# Connector.net
KiCad netlist of a schematic drawn in Altium Designer
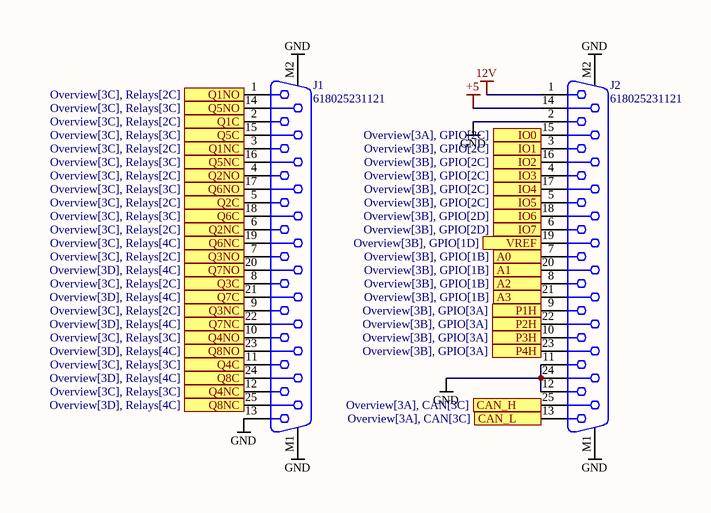
[diagram p0: Connector.SchDoc]

(export (version "E")
  (design (tool "Eeschema 10.0.6"))
  (components
    (comp (ref "J1")
      (value "618025231121")
      (footprint "618025231121")
      (libsource (lib "Altium Content Vault") (part "D-Sub_Female_25p"))
    )
    (comp (ref "J2")
      (value "618025231121")
      (footprint "618025231121")
      (libsource (lib "Altium Content Vault") (part "D-Sub_Female_25p"))
    )
  )
  (nets
    (net (code "1") (name "+5") (class "Default")
      (node (ref "J2") (pin "14") (pinfunction "14_14") (pintype "passive"))
    )
    (net (code "2") (name "/A0") (class "Default")
      (node (ref "J2") (pin "7") (pinfunction "7_7") (pintype "passive"))
    )
    (net (code "3") (name "/A1") (class "Default")
      (node (ref "J2") (pin "20") (pinfunction "20_20") (pintype "passive"))
    )
    (net (code "4") (name "/A2") (class "Default")
      (node (ref "J2") (pin "8") (pinfunction "8_8") (pintype "passive"))
    )
    (net (code "5") (name "/A3") (class "Default")
      (node (ref "J2") (pin "21") (pinfunction "21_21") (pintype "passive"))
    )
    (net (code "6") (name "/CAN_H") (class "Default")
      (node (ref "J2") (pin "25") (pinfunction "25_25") (pintype "passive"))
    )
    (net (code "7") (name "/CAN_L") (class "Default")
      (node (ref "J2") (pin "13") (pinfunction "13_13") (pintype "passive"))
    )
    (net (code "8") (name "/IO0") (class "Default")
      (node (ref "J2") (pin "15") (pinfunction "15_15") (pintype "passive"))
    )
    (net (code "9") (name "/IO1") (class "Default")
      (node (ref "J2") (pin "3") (pinfunction "3_3") (pintype "passive"))
    )
    (net (code "10") (name "/IO2") (class "Default")
      (node (ref "J2") (pin "16") (pinfunction "16_16") (pintype "passive"))
    )
    (net (code "11") (name "/IO3") (class "Default")
      (node (ref "J2") (pin "4") (pinfunction "4_4") (pintype "passive"))
    )
    (net (code "12") (name "/IO4") (class "Default")
      (node (ref "J2") (pin "17") (pinfunction "17_17") (pintype "passive"))
    )
    (net (code "13") (name "/IO5") (class "Default")
      (node (ref "J2") (pin "5") (pinfunction "5_5") (pintype "passive"))
    )
    (net (code "14") (name "/IO6") (class "Default")
      (node (ref "J2") (pin "18") (pinfunction "18_18") (pintype "passive"))
    )
    (net (code "15") (name "/IO7") (class "Default")
      (node (ref "J2") (pin "6") (pinfunction "6_6") (pintype "passive"))
    )
    (net (code "16") (name "/P1H") (class "Default")
      (node (ref "J2") (pin "9") (pinfunction "9_9") (pintype "passive"))
    )
    (net (code "17") (name "/P2H") (class "Default")
      (node (ref "J2") (pin "22") (pinfunction "22_22") (pintype "passive"))
    )
    (net (code "18") (name "/P3H") (class "Default")
      (node (ref "J2") (pin "10") (pinfunction "10_10") (pintype "passive"))
    )
    (net (code "19") (name "/P4H") (class "Default")
      (node (ref "J2") (pin "23") (pinfunction "23_23") (pintype "passive"))
    )
    (net (code "20") (name "/Q1C") (class "Default")
      (node (ref "J1") (pin "2") (pinfunction "2_2") (pintype "passive"))
    )
    (net (code "21") (name "/Q1NC") (class "Default")
      (node (ref "J1") (pin "3") (pinfunction "3_3") (pintype "passive"))
    )
    (net (code "22") (name "/Q1NO") (class "Default")
      (node (ref "J1") (pin "1") (pinfunction "1_1") (pintype "passive"))
    )
    (net (code "23") (name "/Q2C") (class "Default")
      (node (ref "J1") (pin "5") (pinfunction "5_5") (pintype "passive"))
    )
    (net (code "24") (name "/Q2NC") (class "Default")
      (node (ref "J1") (pin "6") (pinfunction "6_6") (pintype "passive"))
    )
    (net (code "25") (name "/Q2NO") (class "Default")
      (node (ref "J1") (pin "4") (pinfunction "4_4") (pintype "passive"))
    )
    (net (code "26") (name "/Q3C") (class "Default")
      (node (ref "J1") (pin "8") (pinfunction "8_8") (pintype "passive"))
    )
    (net (code "27") (name "/Q3NC") (class "Default")
      (node (ref "J1") (pin "9") (pinfunction "9_9") (pintype "passive"))
    )
    (net (code "28") (name "/Q3NO") (class "Default")
      (node (ref "J1") (pin "7") (pinfunction "7_7") (pintype "passive"))
    )
    (net (code "29") (name "/Q4C") (class "Default")
      (node (ref "J1") (pin "11") (pinfunction "11_11") (pintype "passive"))
    )
    (net (code "30") (name "/Q4NC") (class "Default")
      (node (ref "J1") (pin "12") (pinfunction "12_12") (pintype "passive"))
    )
    (net (code "31") (name "/Q4NO") (class "Default")
      (node (ref "J1") (pin "10") (pinfunction "10_10") (pintype "passive"))
    )
    (net (code "32") (name "/Q5C") (class "Default")
      (node (ref "J1") (pin "15") (pinfunction "15_15") (pintype "passive"))
    )
    (net (code "33") (name "/Q5NC") (class "Default")
      (node (ref "J1") (pin "16") (pinfunction "16_16") (pintype "passive"))
    )
    (net (code "34") (name "/Q5NO") (class "Default")
      (node (ref "J1") (pin "14") (pinfunction "14_14") (pintype "passive"))
    )
    (net (code "35") (name "/Q6C") (class "Default")
      (node (ref "J1") (pin "18") (pinfunction "18_18") (pintype "passive"))
    )
    (net (code "36") (name "/Q6NC") (class "Default")
      (node (ref "J1") (pin "19") (pinfunction "19_19") (pintype "passive"))
    )
    (net (code "37") (name "/Q6NO") (class "Default")
      (node (ref "J1") (pin "17") (pinfunction "17_17") (pintype "passive"))
    )
    (net (code "38") (name "/Q7C") (class "Default")
      (node (ref "J1") (pin "21") (pinfunction "21_21") (pintype "passive"))
    )
    (net (code "39") (name "/Q7NC") (class "Default")
      (node (ref "J1") (pin "22") (pinfunction "22_22") (pintype "passive"))
    )
    (net (code "40") (name "/Q7NO") (class "Default")
      (node (ref "J1") (pin "20") (pinfunction "20_20") (pintype "passive"))
    )
    (net (code "41") (name "/Q8C") (class "Default")
      (node (ref "J1") (pin "24") (pinfunction "24_24") (pintype "passive"))
    )
    (net (code "42") (name "/Q8NC") (class "Default")
      (node (ref "J1") (pin "25") (pinfunction "25_25") (pintype "passive"))
    )
    (net (code "43") (name "/Q8NO") (class "Default")
      (node (ref "J1") (pin "23") (pinfunction "23_23") (pintype "passive"))
    )
    (net (code "44") (name "/VREF") (class "Default")
      (node (ref "J2") (pin "19") (pinfunction "19_19") (pintype "passive"))
    )
    (net (code "45") (name "12V") (class "Default")
      (node (ref "J2") (pin "1") (pinfunction "1_1") (pintype "passive"))
    )
    (net (code "46") (name "GND") (class "Default")
      (node (ref "J1") (pin "13") (pinfunction "13_13") (pintype "passive"))
      (node (ref "J1") (pin "M1") (pinfunction "M1_M1") (pintype "passive"))
      (node (ref "J1") (pin "M2") (pinfunction "M2_M2") (pintype "passive"))
      (node (ref "J2") (pin "11") (pinfunction "11_11") (pintype "passive"))
      (node (ref "J2") (pin "12") (pinfunction "12_12") (pintype "passive"))
      (node (ref "J2") (pin "2") (pinfunction "2_2") (pintype "passive"))
      (node (ref "J2") (pin "24") (pinfunction "24_24") (pintype "passive"))
      (node (ref "J2") (pin "M1") (pinfunction "M1_M1") (pintype "passive"))
      (node (ref "J2") (pin "M2") (pinfunction "M2_M2") (pintype "passive"))
    )
  )
)
